# AquaLed-logic.net
KiCad netlist of a schematic drawn in EAGLE
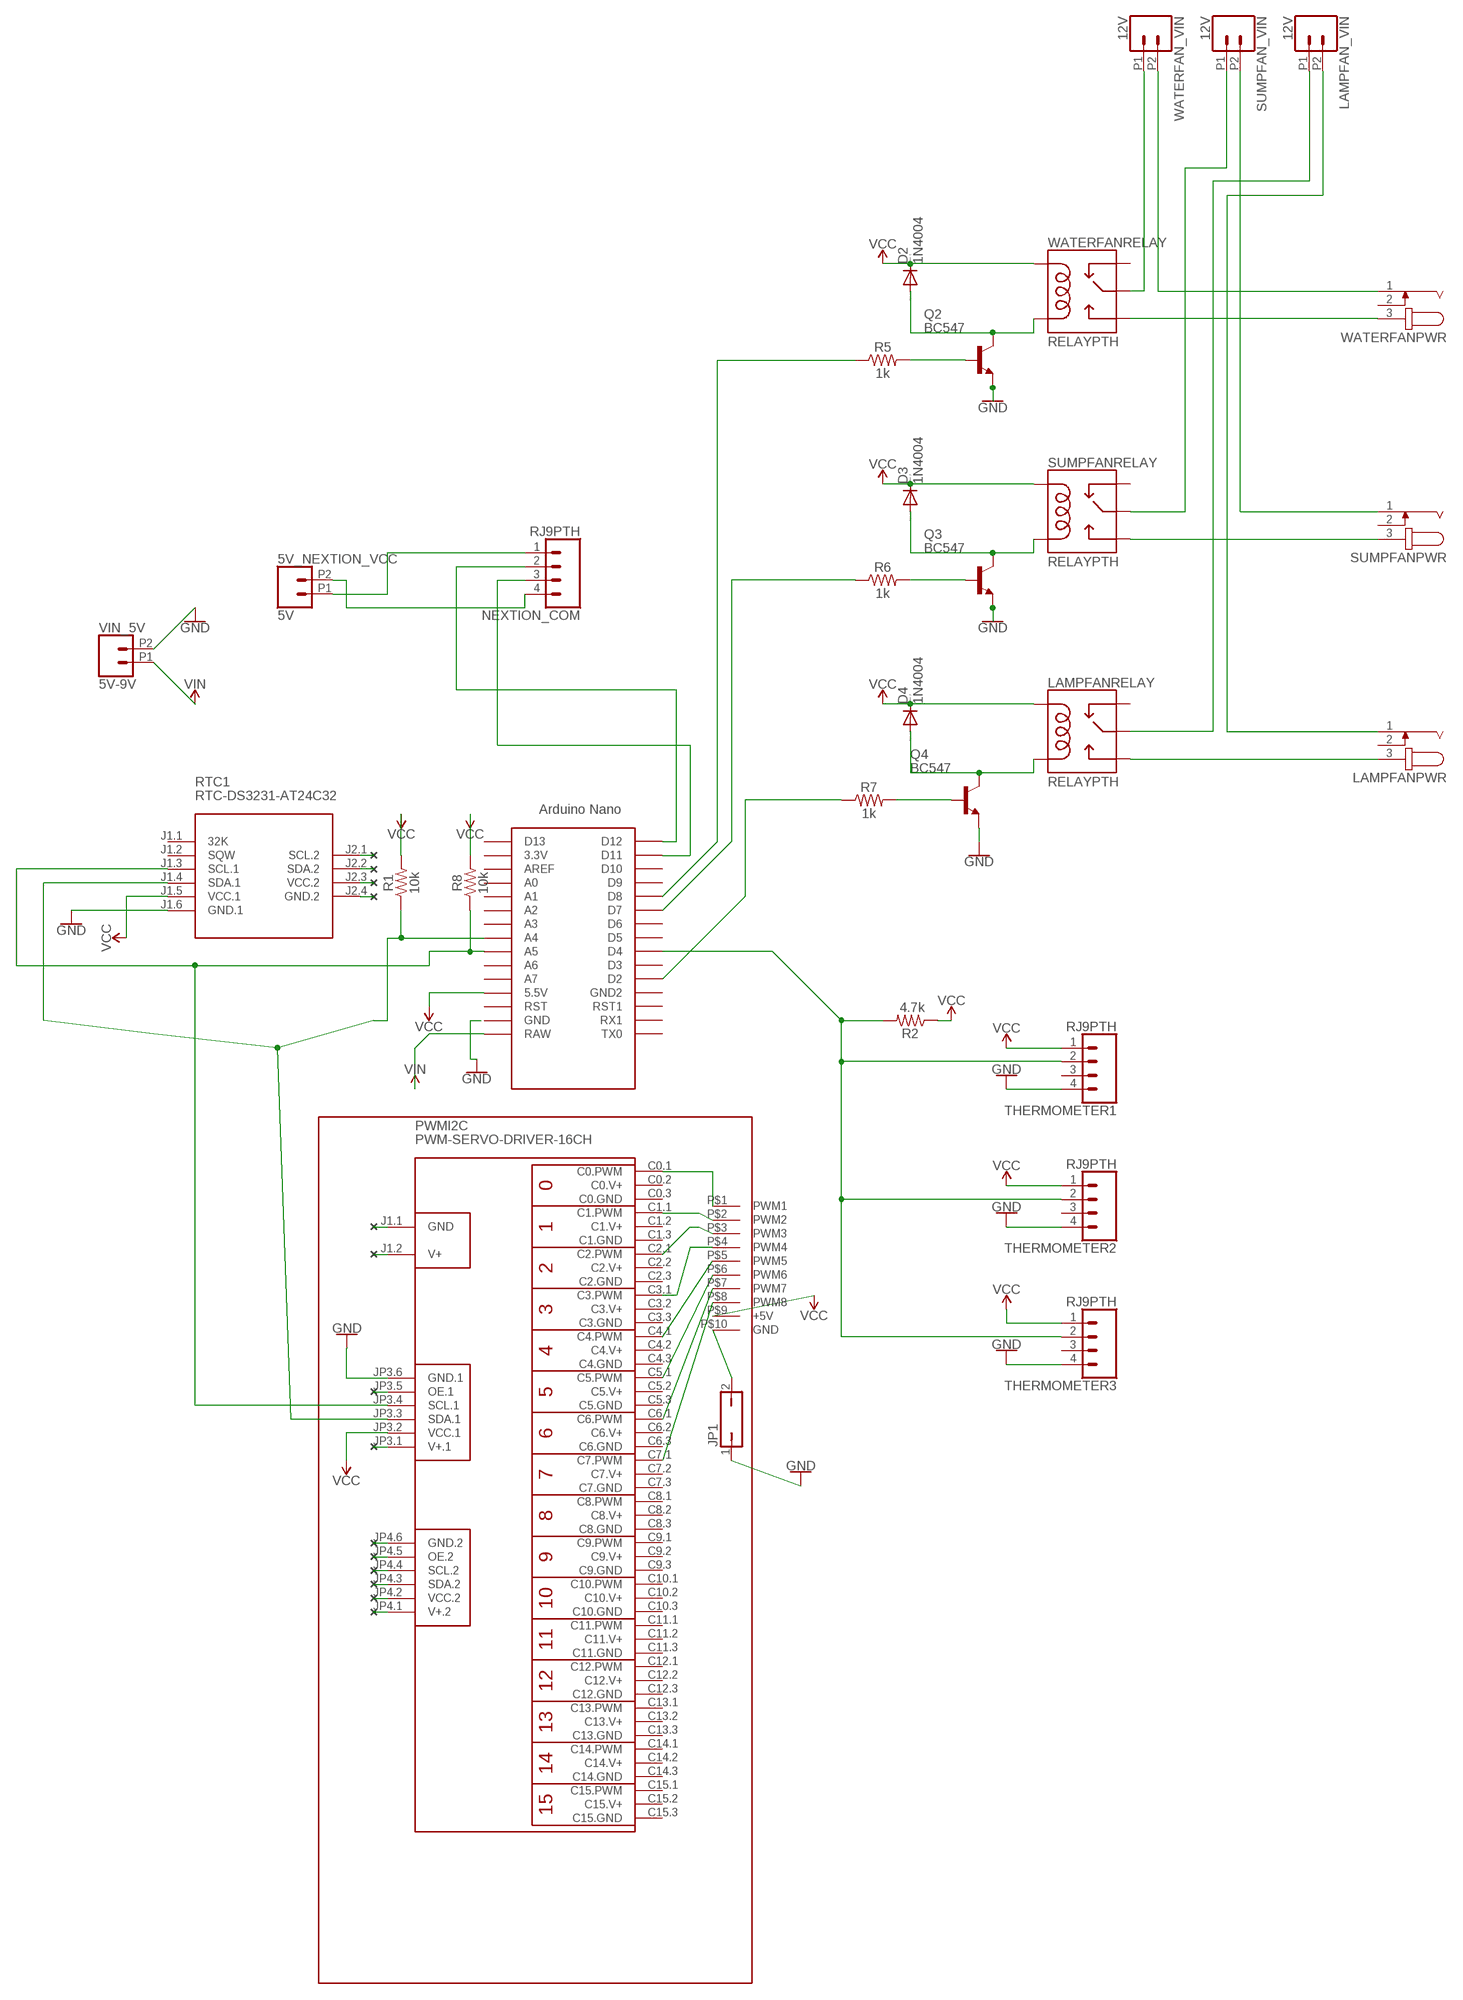
[diagram p0: schematic, sheet 1]

(export (version "E")
  (design (tool "Eeschema 10.0.6"))
  (components
    (comp (ref "5V_NEXTION_VCC")
      (value "5V")
      (footprint "eagle-import:1X02_2.54_SCREWTERM")
      (libsource (lib "eagle-import") (part "CONN_022.54MM_SCREWTERM"))
    )
    (comp (ref "D2")
      (value "1N4004")
      (footprint "eagle-import:DO41-10")
      (libsource (lib "eagle-import") (part "1N4004"))
    )
    (comp (ref "D3")
      (value "1N4004")
      (footprint "eagle-import:DO41-10")
      (libsource (lib "eagle-import") (part "1N4004"))
    )
    (comp (ref "D4")
      (value "1N4004")
      (footprint "eagle-import:DO41-10")
      (libsource (lib "eagle-import") (part "1N4004"))
    )
    (comp (ref "JP1")
      (value "JP1Q")
      (footprint "eagle-import:JP1")
      (libsource (lib "eagle-import") (part "JP1Q"))
    )
    (comp (ref "LAMPFANPWR")
      (value "JACK-PLUG1")
      (footprint "eagle-import:SPC4078")
      (libsource (lib "eagle-import") (part "JACK-PLUG1"))
    )
    (comp (ref "LAMPFANRELAY")
      (value "RELAYPTH")
      (footprint "eagle-import:SRD-05VDC-SL-C")
      (libsource (lib "eagle-import") (part "RELAYPTH"))
    )
    (comp (ref "LAMPFAN_VIN")
      (value "12V")
      (footprint "eagle-import:1X02_2.54_SCREWTERM")
      (libsource (lib "eagle-import") (part "CONN_022.54MM_SCREWTERM"))
    )
    (comp (ref "NEXTION_COM")
      (value "RJ9PTH")
      (footprint "eagle-import:RJ9")
      (libsource (lib "eagle-import") (part "RJ9PTH"))
    )
    (comp (ref "PWMI2C")
      (value "PWM-SERVO-DRIVER-16CH")
      (footprint "eagle-import:PWM-SERVO-DRIVER-16CH")
      (libsource (lib "eagle-import") (part "PWM-SERVO-DRIVER-16CH"))
    )
    (comp (ref "Q2")
      (value "BC547")
      (footprint "eagle-import:TO92")
      (libsource (lib "eagle-import") (part "BC547"))
    )
    (comp (ref "Q3")
      (value "BC547")
      (footprint "eagle-import:TO92")
      (libsource (lib "eagle-import") (part "BC547"))
    )
    (comp (ref "Q4")
      (value "BC547")
      (footprint "eagle-import:TO92")
      (libsource (lib "eagle-import") (part "BC547"))
    )
    (comp (ref "R1")
      (value "10k")
      (footprint "eagle-import:AXIAL-0.3")
      (libsource (lib "eagle-import") (part "SparkFun-Resistors_532_10KOHM-HORIZ-1/6W-5%"))
    )
    (comp (ref "R2")
      (value "4.7k")
      (footprint "eagle-import:AXIAL-0.3")
      (libsource (lib "eagle-import") (part "RESISTORAXIAL-0.3"))
    )
    (comp (ref "R5")
      (value "1k")
      (footprint "eagle-import:AXIAL-0.3")
      (libsource (lib "eagle-import") (part "10KOHM-HORIZ-1/4W-1%"))
    )
    (comp (ref "R6")
      (value "1k")
      (footprint "eagle-import:AXIAL-0.3")
      (libsource (lib "eagle-import") (part "10KOHM-HORIZ-1/4W-1%"))
    )
    (comp (ref "R7")
      (value "1k")
      (footprint "eagle-import:AXIAL-0.3")
      (libsource (lib "eagle-import") (part "10KOHM-HORIZ-1/4W-1%"))
    )
    (comp (ref "R8")
      (value "10k")
      (footprint "eagle-import:AXIAL-0.3")
      (libsource (lib "eagle-import") (part "SparkFun-Resistors_532_10KOHM-HORIZ-1/6W-5%"))
    )
    (comp (ref "RTC1")
      (value "RTC-DS3231-AT24C32")
      (footprint "eagle-import:RTC-DS3231-AT24C32")
      (fields (field (name "SPICEPREFIX") "X"))
      (libsource (lib "eagle-import") (part "RTC-DS3231-AT24C32"))
    )
    (comp (ref "SUMPFANPWR")
      (value "JACK-PLUG1")
      (footprint "eagle-import:SPC4078")
      (libsource (lib "eagle-import") (part "JACK-PLUG1"))
    )
    (comp (ref "SUMPFANRELAY")
      (value "RELAYPTH")
      (footprint "eagle-import:SRD-05VDC-SL-C")
      (libsource (lib "eagle-import") (part "RELAYPTH"))
    )
    (comp (ref "SUMPFAN_VIN")
      (value "12V")
      (footprint "eagle-import:1X02_2.54_SCREWTERM")
      (libsource (lib "eagle-import") (part "CONN_022.54MM_SCREWTERM"))
    )
    (comp (ref "THERMOMETER1")
      (value "RJ9PTH")
      (footprint "eagle-import:RJ9")
      (libsource (lib "eagle-import") (part "RJ9PTH"))
    )
    (comp (ref "THERMOMETER2")
      (value "RJ9PTH")
      (footprint "eagle-import:RJ9")
      (libsource (lib "eagle-import") (part "RJ9PTH"))
    )
    (comp (ref "THERMOMETER3")
      (value "RJ9PTH")
      (footprint "eagle-import:RJ9")
      (libsource (lib "eagle-import") (part "RJ9PTH"))
    )
    (comp (ref "U$1")
      (value "NANO")
      (footprint "eagle-import:NANO")
      (libsource (lib "eagle-import") (part "NANO"))
    )
    (comp (ref "U$29")
      (value "PCB")
      (footprint "eagle-import:PCB")
      (libsource (lib "eagle-import") (part "PCB"))
    )
    (comp (ref "VIN_5V")
      (value "5V-9V")
      (footprint "eagle-import:1X02_2.54_SCREWTERM")
      (libsource (lib "eagle-import") (part "CONN_022.54MM_SCREWTERM"))
    )
    (comp (ref "WATERFANPWR")
      (value "JACK-PLUG1")
      (footprint "eagle-import:SPC4078")
      (libsource (lib "eagle-import") (part "JACK-PLUG1"))
    )
    (comp (ref "WATERFANRELAY")
      (value "RELAYPTH")
      (footprint "eagle-import:SRD-05VDC-SL-C")
      (libsource (lib "eagle-import") (part "RELAYPTH"))
    )
    (comp (ref "WATERFAN_VIN")
      (value "12V")
      (footprint "eagle-import:1X02_2.54_SCREWTERM")
      (libsource (lib "eagle-import") (part "CONN_022.54MM_SCREWTERM"))
    )
  )
  (nets
    (net (code "1") (name "GND") (class "Default")
      (node (ref "JP1") (pin "1") (pinfunction "1_1") (pintype "passive"))
      (node (ref "PWMI2C") (pin "JP3.6") (pinfunction "GND.1_JP3.6") (pintype "power_in"))
      (node (ref "Q2") (pin "1") (pinfunction "E_1") (pintype "passive"))
      (node (ref "Q3") (pin "1") (pinfunction "E_1") (pintype "passive"))
      (node (ref "Q4") (pin "1") (pinfunction "E_1") (pintype "passive"))
      (node (ref "RTC1") (pin "J1.6") (pinfunction "GND.1_J1.6") (pintype "power_in"))
      (node (ref "THERMOMETER1") (pin "4") (pinfunction "4_4") (pintype "passive"))
      (node (ref "THERMOMETER2") (pin "4") (pinfunction "4_4") (pintype "passive"))
      (node (ref "THERMOMETER3") (pin "4") (pinfunction "4_4") (pintype "passive"))
      (node (ref "U$1") (pin "GND") (pinfunction "GND_GND") (pintype "bidirectional"))
      (node (ref "VIN_5V") (pin "P2") (pinfunction "2_P2") (pintype "passive"))
    )
    (net (code "2") (name "Net-(5V_NEXTION_VCC-1)") (class "Default")
      (node (ref "5V_NEXTION_VCC") (pin "P1") (pinfunction "1_P1") (pintype "passive"))
      (node (ref "NEXTION_COM") (pin "1") (pinfunction "1_1") (pintype "passive"))
    )
    (net (code "3") (name "Net-(5V_NEXTION_VCC-2)") (class "Default")
      (node (ref "5V_NEXTION_VCC") (pin "P2") (pinfunction "2_P2") (pintype "passive"))
      (node (ref "NEXTION_COM") (pin "4") (pinfunction "4_4") (pintype "passive"))
    )
    (net (code "4") (name "Net-(LAMPFANPWR-Pad3)") (class "Default")
      (node (ref "LAMPFANPWR") (pin "3") (pinfunction "3_3") (pintype "passive"))
      (node (ref "LAMPFANRELAY") (pin "SWOPEN") (pinfunction "SWOPEN_SWOPEN") (pintype "bidirectional"))
    )
    (net (code "5") (name "Net-(LAMPFAN_VIN-1)") (class "Default")
      (node (ref "LAMPFANRELAY") (pin "SWCOMMON") (pinfunction "SWCOMMON_SWCOMMON") (pintype "bidirectional"))
      (node (ref "LAMPFAN_VIN") (pin "P1") (pinfunction "1_P1") (pintype "passive"))
    )
    (net (code "6") (name "Net-(LAMPFAN_VIN-2)") (class "Default")
      (node (ref "LAMPFANPWR") (pin "1") (pinfunction "1_1") (pintype "passive"))
      (node (ref "LAMPFAN_VIN") (pin "P2") (pinfunction "2_P2") (pintype "passive"))
    )
    (net (code "7") (name "Net-(NEXTION_COM-Pad2)") (class "Default")
      (node (ref "NEXTION_COM") (pin "2") (pinfunction "2_2") (pintype "passive"))
      (node (ref "U$1") (pin "D12") (pinfunction "D12_D12") (pintype "bidirectional"))
    )
    (net (code "8") (name "Net-(NEXTION_COM-Pad3)") (class "Default")
      (node (ref "NEXTION_COM") (pin "3") (pinfunction "3_3") (pintype "passive"))
      (node (ref "U$1") (pin "D11") (pinfunction "D11_D11") (pintype "bidirectional"))
    )
    (net (code "9") (name "Net-(PWMI2C-C0.PWM)") (class "Default")
      (node (ref "PWMI2C") (pin "C0.1") (pinfunction "C0.PWM_C0.1") (pintype "bidirectional"))
      (node (ref "U$29") (pin "P$1") (pinfunction "PWM1_P$1") (pintype "bidirectional"))
    )
    (net (code "10") (name "Net-(PWMI2C-C1.PWM)") (class "Default")
      (node (ref "PWMI2C") (pin "C1.1") (pinfunction "C1.PWM_C1.1") (pintype "bidirectional"))
      (node (ref "U$29") (pin "P$2") (pinfunction "PWM2_P$2") (pintype "bidirectional"))
    )
    (net (code "11") (name "Net-(PWMI2C-C2.PWM)") (class "Default")
      (node (ref "PWMI2C") (pin "C2.1") (pinfunction "C2.PWM_C2.1") (pintype "bidirectional"))
      (node (ref "U$29") (pin "P$3") (pinfunction "PWM3_P$3") (pintype "bidirectional"))
    )
    (net (code "12") (name "Net-(PWMI2C-C3.PWM)") (class "Default")
      (node (ref "PWMI2C") (pin "C3.1") (pinfunction "C3.PWM_C3.1") (pintype "bidirectional"))
      (node (ref "U$29") (pin "P$4") (pinfunction "PWM4_P$4") (pintype "bidirectional"))
    )
    (net (code "13") (name "Net-(PWMI2C-C4.PWM)") (class "Default")
      (node (ref "PWMI2C") (pin "C4.1") (pinfunction "C4.PWM_C4.1") (pintype "bidirectional"))
      (node (ref "U$29") (pin "P$5") (pinfunction "PWM5_P$5") (pintype "bidirectional"))
    )
    (net (code "14") (name "Net-(PWMI2C-C5.PWM)") (class "Default")
      (node (ref "PWMI2C") (pin "C5.1") (pinfunction "C5.PWM_C5.1") (pintype "bidirectional"))
      (node (ref "U$29") (pin "P$6") (pinfunction "PWM6_P$6") (pintype "bidirectional"))
    )
    (net (code "15") (name "Net-(PWMI2C-C6.PWM)") (class "Default")
      (node (ref "PWMI2C") (pin "C6.1") (pinfunction "C6.PWM_C6.1") (pintype "bidirectional"))
      (node (ref "U$29") (pin "P$7") (pinfunction "PWM7_P$7") (pintype "bidirectional"))
    )
    (net (code "16") (name "Net-(PWMI2C-C7.PWM)") (class "Default")
      (node (ref "PWMI2C") (pin "C7.1") (pinfunction "C7.PWM_C7.1") (pintype "bidirectional"))
      (node (ref "U$29") (pin "P$8") (pinfunction "PWM8_P$8") (pintype "bidirectional"))
    )
    (net (code "17") (name "Net-(PWMI2C-SCL.1)") (class "Default")
      (node (ref "PWMI2C") (pin "JP3.4") (pinfunction "SCL.1_JP3.4") (pintype "bidirectional"))
      (node (ref "R8") (pin "P$1") (pinfunction "1_P$1") (pintype "passive"))
      (node (ref "RTC1") (pin "J1.3") (pinfunction "SCL.1_J1.3") (pintype "bidirectional"))
      (node (ref "U$1") (pin "A5") (pinfunction "A5_A5") (pintype "bidirectional"))
    )
    (net (code "18") (name "Net-(PWMI2C-SDA.1)") (class "Default")
      (node (ref "PWMI2C") (pin "JP3.3") (pinfunction "SDA.1_JP3.3") (pintype "bidirectional"))
      (node (ref "R1") (pin "P$1") (pinfunction "1_P$1") (pintype "passive"))
      (node (ref "RTC1") (pin "J1.4") (pinfunction "SDA.1_J1.4") (pintype "bidirectional"))
      (node (ref "U$1") (pin "A4") (pinfunction "A4_A4") (pintype "bidirectional"))
    )
    (net (code "19") (name "Net-(Q2-B)") (class "Default")
      (node (ref "Q2") (pin "2") (pinfunction "B_2") (pintype "passive"))
      (node (ref "R5") (pin "P$2") (pinfunction "2_P$2") (pintype "passive"))
    )
    (net (code "20") (name "Net-(Q2-C)") (class "Default")
      (node (ref "D2") (pin "A") (pinfunction "A_A") (pintype "passive"))
      (node (ref "Q2") (pin "3") (pinfunction "C_3") (pintype "passive"))
      (node (ref "WATERFANRELAY") (pin "COIL0") (pinfunction "COIL0_COIL0") (pintype "bidirectional"))
    )
    (net (code "21") (name "Net-(Q3-B)") (class "Default")
      (node (ref "Q3") (pin "2") (pinfunction "B_2") (pintype "passive"))
      (node (ref "R6") (pin "P$2") (pinfunction "2_P$2") (pintype "passive"))
    )
    (net (code "22") (name "Net-(Q3-C)") (class "Default")
      (node (ref "D3") (pin "A") (pinfunction "A_A") (pintype "passive"))
      (node (ref "Q3") (pin "3") (pinfunction "C_3") (pintype "passive"))
      (node (ref "SUMPFANRELAY") (pin "COIL0") (pinfunction "COIL0_COIL0") (pintype "bidirectional"))
    )
    (net (code "23") (name "Net-(Q4-B)") (class "Default")
      (node (ref "Q4") (pin "2") (pinfunction "B_2") (pintype "passive"))
      (node (ref "R7") (pin "P$2") (pinfunction "2_P$2") (pintype "passive"))
    )
    (net (code "24") (name "Net-(Q4-C)") (class "Default")
      (node (ref "D4") (pin "A") (pinfunction "A_A") (pintype "passive"))
      (node (ref "LAMPFANRELAY") (pin "COIL0") (pinfunction "COIL0_COIL0") (pintype "bidirectional"))
      (node (ref "Q4") (pin "3") (pinfunction "C_3") (pintype "passive"))
    )
    (net (code "25") (name "Net-(R2-2)") (class "Default")
      (node (ref "R2") (pin "P$2") (pinfunction "2_P$2") (pintype "passive"))
      (node (ref "THERMOMETER1") (pin "2") (pinfunction "2_2") (pintype "passive"))
      (node (ref "THERMOMETER2") (pin "2") (pinfunction "2_2") (pintype "passive"))
      (node (ref "THERMOMETER3") (pin "2") (pinfunction "2_2") (pintype "passive"))
      (node (ref "U$1") (pin "D4") (pinfunction "D4_D4") (pintype "bidirectional"))
    )
    (net (code "26") (name "Net-(R5-1)") (class "Default")
      (node (ref "R5") (pin "P$1") (pinfunction "1_P$1") (pintype "passive"))
      (node (ref "U$1") (pin "D8") (pinfunction "D8_D8") (pintype "bidirectional"))
    )
    (net (code "27") (name "Net-(R6-1)") (class "Default")
      (node (ref "R6") (pin "P$1") (pinfunction "1_P$1") (pintype "passive"))
      (node (ref "U$1") (pin "D7") (pinfunction "D7_D7") (pintype "bidirectional"))
    )
    (net (code "28") (name "Net-(R7-1)") (class "Default")
      (node (ref "R7") (pin "P$1") (pinfunction "1_P$1") (pintype "passive"))
      (node (ref "U$1") (pin "D2") (pinfunction "D2_D2") (pintype "bidirectional"))
    )
    (net (code "29") (name "Net-(SUMPFANPWR-Pad3)") (class "Default")
      (node (ref "SUMPFANPWR") (pin "3") (pinfunction "3_3") (pintype "passive"))
      (node (ref "SUMPFANRELAY") (pin "SWOPEN") (pinfunction "SWOPEN_SWOPEN") (pintype "bidirectional"))
    )
    (net (code "30") (name "Net-(SUMPFAN_VIN-1)") (class "Default")
      (node (ref "SUMPFANRELAY") (pin "SWCOMMON") (pinfunction "SWCOMMON_SWCOMMON") (pintype "bidirectional"))
      (node (ref "SUMPFAN_VIN") (pin "P1") (pinfunction "1_P1") (pintype "passive"))
    )
    (net (code "31") (name "Net-(SUMPFAN_VIN-2)") (class "Default")
      (node (ref "SUMPFANPWR") (pin "1") (pinfunction "1_1") (pintype "passive"))
      (node (ref "SUMPFAN_VIN") (pin "P2") (pinfunction "2_P2") (pintype "passive"))
    )
    (net (code "32") (name "Net-(U$29-GND)") (class "Default")
      (node (ref "JP1") (pin "2") (pinfunction "2_2") (pintype "passive"))
      (node (ref "U$29") (pin "P$10") (pinfunction "GND_P$10") (pintype "power_in"))
    )
    (net (code "33") (name "Net-(WATERFANPWR-Pad3)") (class "Default")
      (node (ref "WATERFANPWR") (pin "3") (pinfunction "3_3") (pintype "passive"))
      (node (ref "WATERFANRELAY") (pin "SWOPEN") (pinfunction "SWOPEN_SWOPEN") (pintype "bidirectional"))
    )
    (net (code "34") (name "Net-(WATERFAN_VIN-1)") (class "Default")
      (node (ref "WATERFANRELAY") (pin "SWCOMMON") (pinfunction "SWCOMMON_SWCOMMON") (pintype "bidirectional"))
      (node (ref "WATERFAN_VIN") (pin "P1") (pinfunction "1_P1") (pintype "passive"))
    )
    (net (code "35") (name "Net-(WATERFAN_VIN-2)") (class "Default")
      (node (ref "WATERFANPWR") (pin "1") (pinfunction "1_1") (pintype "passive"))
      (node (ref "WATERFAN_VIN") (pin "P2") (pinfunction "2_P2") (pintype "passive"))
    )
    (net (code "36") (name "VCC") (class "Default")
      (node (ref "D2") (pin "C") (pinfunction "C_C") (pintype "passive"))
      (node (ref "D3") (pin "C") (pinfunction "C_C") (pintype "passive"))
      (node (ref "D4") (pin "C") (pinfunction "C_C") (pintype "passive"))
      (node (ref "LAMPFANRELAY") (pin "COIL1") (pinfunction "COIL1_COIL1") (pintype "bidirectional"))
      (node (ref "PWMI2C") (pin "JP3.2") (pinfunction "VCC.1_JP3.2") (pintype "power_in"))
      (node (ref "R1") (pin "P$2") (pinfunction "2_P$2") (pintype "passive"))
      (node (ref "R2") (pin "P$1") (pinfunction "1_P$1") (pintype "passive"))
      (node (ref "R8") (pin "P$2") (pinfunction "2_P$2") (pintype "passive"))
      (node (ref "RTC1") (pin "J1.5") (pinfunction "VCC.1_J1.5") (pintype "power_in"))
      (node (ref "SUMPFANRELAY") (pin "COIL1") (pinfunction "COIL1_COIL1") (pintype "bidirectional"))
      (node (ref "THERMOMETER1") (pin "1") (pinfunction "1_1") (pintype "passive"))
      (node (ref "THERMOMETER2") (pin "1") (pinfunction "1_1") (pintype "passive"))
      (node (ref "THERMOMETER3") (pin "1") (pinfunction "1_1") (pintype "passive"))
      (node (ref "U$1") (pin "5V") (pinfunction "5.5V_5V") (pintype "bidirectional"))
      (node (ref "U$29") (pin "P$9") (pinfunction "+5V_P$9") (pintype "power_in"))
      (node (ref "WATERFANRELAY") (pin "COIL1") (pinfunction "COIL1_COIL1") (pintype "bidirectional"))
    )
    (net (code "37") (name "VIN") (class "Default")
      (node (ref "U$1") (pin "RAW") (pinfunction "RAW_RAW") (pintype "bidirectional"))
      (node (ref "VIN_5V") (pin "P1") (pinfunction "1_P1") (pintype "passive"))
    )
    (net (code "38") (name "unconnected-(LAMPFANPWR-Pad2)") (class "Default")
      (node (ref "LAMPFANPWR") (pin "2") (pinfunction "2_2") (pintype "passive"))
    )
    (net (code "39") (name "unconnected-(LAMPFANRELAY-SWCLOSE-PadSWCLOSED)") (class "Default")
      (node (ref "LAMPFANRELAY") (pin "SWCLOSED") (pinfunction "SWCLOSE_SWCLOSED") (pintype "bidirectional"))
    )
    (net (code "40") (name "unconnected-(PWMI2C-C0.GND-PadC0.3)") (class "Default")
      (node (ref "PWMI2C") (pin "C0.3") (pinfunction "C0.GND_C0.3") (pintype "bidirectional"))
    )
    (net (code "41") (name "unconnected-(PWMI2C-C0.V+-PadC0.2)") (class "Default")
      (node (ref "PWMI2C") (pin "C0.2") (pinfunction "C0.V+_C0.2") (pintype "bidirectional"))
    )
    (net (code "42") (name "unconnected-(PWMI2C-C1.GND-PadC1.3)") (class "Default")
      (node (ref "PWMI2C") (pin "C1.3") (pinfunction "C1.GND_C1.3") (pintype "bidirectional"))
    )
    (net (code "43") (name "unconnected-(PWMI2C-C1.V+-PadC1.2)") (class "Default")
      (node (ref "PWMI2C") (pin "C1.2") (pinfunction "C1.V+_C1.2") (pintype "bidirectional"))
    )
    (net (code "44") (name "unconnected-(PWMI2C-C2.GND-PadC2.3)") (class "Default")
      (node (ref "PWMI2C") (pin "C2.3") (pinfunction "C2.GND_C2.3") (pintype "bidirectional"))
    )
    (net (code "45") (name "unconnected-(PWMI2C-C2.V+-PadC2.2)") (class "Default")
      (node (ref "PWMI2C") (pin "C2.2") (pinfunction "C2.V+_C2.2") (pintype "bidirectional"))
    )
    (net (code "46") (name "unconnected-(PWMI2C-C3.GND-PadC3.3)") (class "Default")
      (node (ref "PWMI2C") (pin "C3.3") (pinfunction "C3.GND_C3.3") (pintype "bidirectional"))
    )
    (net (code "47") (name "unconnected-(PWMI2C-C3.V+-PadC3.2)") (class "Default")
      (node (ref "PWMI2C") (pin "C3.2") (pinfunction "C3.V+_C3.2") (pintype "bidirectional"))
    )
    (net (code "48") (name "unconnected-(PWMI2C-C4.GND-PadC4.3)") (class "Default")
      (node (ref "PWMI2C") (pin "C4.3") (pinfunction "C4.GND_C4.3") (pintype "bidirectional"))
    )
    (net (code "49") (name "unconnected-(PWMI2C-C4.V+-PadC4.2)") (class "Default")
      (node (ref "PWMI2C") (pin "C4.2") (pinfunction "C4.V+_C4.2") (pintype "bidirectional"))
    )
    (net (code "50") (name "unconnected-(PWMI2C-C5.GND-PadC5.3)") (class "Default")
      (node (ref "PWMI2C") (pin "C5.3") (pinfunction "C5.GND_C5.3") (pintype "bidirectional"))
    )
    (net (code "51") (name "unconnected-(PWMI2C-C5.V+-PadC5.2)") (class "Default")
      (node (ref "PWMI2C") (pin "C5.2") (pinfunction "C5.V+_C5.2") (pintype "bidirectional"))
    )
    (net (code "52") (name "unconnected-(PWMI2C-C6.GND-PadC6.3)") (class "Default")
      (node (ref "PWMI2C") (pin "C6.3") (pinfunction "C6.GND_C6.3") (pintype "bidirectional"))
    )
    (net (code "53") (name "unconnected-(PWMI2C-C6.V+-PadC6.2)") (class "Default")
      (node (ref "PWMI2C") (pin "C6.2") (pinfunction "C6.V+_C6.2") (pintype "bidirectional"))
    )
    (net (code "54") (name "unconnected-(PWMI2C-C7.GND-PadC7.3)") (class "Default")
      (node (ref "PWMI2C") (pin "C7.3") (pinfunction "C7.GND_C7.3") (pintype "bidirectional"))
    )
    (net (code "55") (name "unconnected-(PWMI2C-C7.V+-PadC7.2)") (class "Default")
      (node (ref "PWMI2C") (pin "C7.2") (pinfunction "C7.V+_C7.2") (pintype "bidirectional"))
    )
    (net (code "56") (name "unconnected-(PWMI2C-C8.GND-PadC8.3)") (class "Default")
      (node (ref "PWMI2C") (pin "C8.3") (pinfunction "C8.GND_C8.3") (pintype "bidirectional"))
    )
    (net (code "57") (name "unconnected-(PWMI2C-C8.PWM-PadC8.1)") (class "Default")
      (node (ref "PWMI2C") (pin "C8.1") (pinfunction "C8.PWM_C8.1") (pintype "bidirectional"))
    )
    (net (code "58") (name "unconnected-(PWMI2C-C8.V+-PadC8.2)") (class "Default")
      (node (ref "PWMI2C") (pin "C8.2") (pinfunction "C8.V+_C8.2") (pintype "bidirectional"))
    )
    (net (code "59") (name "unconnected-(PWMI2C-C9.GND-PadC9.3)") (class "Default")
      (node (ref "PWMI2C") (pin "C9.3") (pinfunction "C9.GND_C9.3") (pintype "bidirectional"))
    )
    (net (code "60") (name "unconnected-(PWMI2C-C9.PWM-PadC9.1)") (class "Default")
      (node (ref "PWMI2C") (pin "C9.1") (pinfunction "C9.PWM_C9.1") (pintype "bidirectional"))
    )
    (net (code "61") (name "unconnected-(PWMI2C-C9.V+-PadC9.2)") (class "Default")
      (node (ref "PWMI2C") (pin "C9.2") (pinfunction "C9.V+_C9.2") (pintype "bidirectional"))
    )
    (net (code "62") (name "unconnected-(PWMI2C-C10.GND-PadC10.3)") (class "Default")
      (node (ref "PWMI2C") (pin "C10.3") (pinfunction "C10.GND_C10.3") (pintype "bidirectional"))
    )
    (net (code "63") (name "unconnected-(PWMI2C-C10.PWM-PadC10.1)") (class "Default")
      (node (ref "PWMI2C") (pin "C10.1") (pinfunction "C10.PWM_C10.1") (pintype "bidirectional"))
    )
    (net (code "64") (name "unconnected-(PWMI2C-C10.V+-PadC10.2)") (class "Default")
      (node (ref "PWMI2C") (pin "C10.2") (pinfunction "C10.V+_C10.2") (pintype "bidirectional"))
    )
    (net (code "65") (name "unconnected-(PWMI2C-C11.GND-PadC11.3)") (class "Default")
      (node (ref "PWMI2C") (pin "C11.3") (pinfunction "C11.GND_C11.3") (pintype "bidirectional"))
    )
    (net (code "66") (name "unconnected-(PWMI2C-C11.PWM-PadC11.1)") (class "Default")
      (node (ref "PWMI2C") (pin "C11.1") (pinfunction "C11.PWM_C11.1") (pintype "bidirectional"))
    )
    (net (code "67") (name "unconnected-(PWMI2C-C11.V+-PadC11.2)") (class "Default")
      (node (ref "PWMI2C") (pin "C11.2") (pinfunction "C11.V+_C11.2") (pintype "bidirectional"))
    )
    (net (code "68") (name "unconnected-(PWMI2C-C12.GND-PadC12.3)") (class "Default")
      (node (ref "PWMI2C") (pin "C12.3") (pinfunction "C12.GND_C12.3") (pintype "bidirectional"))
    )
    (net (code "69") (name "unconnected-(PWMI2C-C12.PWM-PadC12.1)") (class "Default")
      (node (ref "PWMI2C") (pin "C12.1") (pinfunction "C12.PWM_C12.1") (pintype "bidirectional"))
    )
    (net (code "70") (name "unconnected-(PWMI2C-C12.V+-PadC12.2)") (class "Default")
      (node (ref "PWMI2C") (pin "C12.2") (pinfunction "C12.V+_C12.2") (pintype "bidirectional"))
    )
    (net (code "71") (name "unconnected-(PWMI2C-C13.GND-PadC13.3)") (class "Default")
      (node (ref "PWMI2C") (pin "C13.3") (pinfunction "C13.GND_C13.3") (pintype "bidirectional"))
    )
    (net (code "72") (name "unconnected-(PWMI2C-C13.PWM-PadC13.1)") (class "Default")
      (node (ref "PWMI2C") (pin "C13.1") (pinfunction "C13.PWM_C13.1") (pintype "bidirectional"))
    )
    (net (code "73") (name "unconnected-(PWMI2C-C13.V+-PadC13.2)") (class "Default")
      (node (ref "PWMI2C") (pin "C13.2") (pinfunction "C13.V+_C13.2") (pintype "bidirectional"))
    )
    (net (code "74") (name "unconnected-(PWMI2C-C14.GND-PadC14.3)") (class "Default")
      (node (ref "PWMI2C") (pin "C14.3") (pinfunction "C14.GND_C14.3") (pintype "bidirectional"))
    )
    (net (code "75") (name "unconnected-(PWMI2C-C14.PWM-PadC14.1)") (class "Default")
      (node (ref "PWMI2C") (pin "C14.1") (pinfunction "C14.PWM_C14.1") (pintype "bidirectional"))
    )
    (net (code "76") (name "unconnected-(PWMI2C-C14.V+-PadC14.2)") (class "Default")
      (node (ref "PWMI2C") (pin "C14.2") (pinfunction "C14.V+_C14.2") (pintype "bidirectional"))
    )
    (net (code "77") (name "unconnected-(PWMI2C-C15.GND-PadC15.3)") (class "Default")
      (node (ref "PWMI2C") (pin "C15.3") (pinfunction "C15.GND_C15.3") (pintype "bidirectional"))
    )
    (net (code "78") (name "unconnected-(PWMI2C-C15.PWM-PadC15.1)") (class "Default")
      (node (ref "PWMI2C") (pin "C15.1") (pinfunction "C15.PWM_C15.1") (pintype "bidirectional"))
    )
    (net (code "79") (name "unconnected-(PWMI2C-C15.V+-PadC15.2)") (class "Default")
      (node (ref "PWMI2C") (pin "C15.2") (pinfunction "C15.V+_C15.2") (pintype "bidirectional"))
    )
    (net (code "80") (name "unconnected-(PWMI2C-GND-PadJ1.1)") (class "Default")
      (node (ref "PWMI2C") (pin "J1.1") (pinfunction "GND_J1.1") (pintype "power_in"))
    )
    (net (code "81") (name "unconnected-(PWMI2C-GND.2-PadJP4.6)") (class "Default")
      (node (ref "PWMI2C") (pin "JP4.6") (pinfunction "GND.2_JP4.6") (pintype "power_in"))
    )
    (net (code "82") (name "unconnected-(PWMI2C-OE.1-PadJP3.5)") (class "Default")
      (node (ref "PWMI2C") (pin "JP3.5") (pinfunction "OE.1_JP3.5") (pintype "bidirectional"))
    )
    (net (code "83") (name "unconnected-(PWMI2C-OE.2-PadJP4.5)") (class "Default")
      (node (ref "PWMI2C") (pin "JP4.5") (pinfunction "OE.2_JP4.5") (pintype "bidirectional"))
    )
    (net (code "84") (name "unconnected-(PWMI2C-SCL.2-PadJP4.4)") (class "Default")
      (node (ref "PWMI2C") (pin "JP4.4") (pinfunction "SCL.2_JP4.4") (pintype "bidirectional"))
    )
    (net (code "85") (name "unconnected-(PWMI2C-SDA.2-PadJP4.3)") (class "Default")
      (node (ref "PWMI2C") (pin "JP4.3") (pinfunction "SDA.2_JP4.3") (pintype "bidirectional"))
    )
    (net (code "86") (name "unconnected-(PWMI2C-V+-PadJ1.2)") (class "Default")
      (node (ref "PWMI2C") (pin "J1.2") (pinfunction "V+_J1.2") (pintype "power_in"))
    )
    (net (code "87") (name "unconnected-(PWMI2C-V+.1-PadJP3.1)") (class "Default")
      (node (ref "PWMI2C") (pin "JP3.1") (pinfunction "V+.1_JP3.1") (pintype "power_in"))
    )
    (net (code "88") (name "unconnected-(PWMI2C-V+.2-PadJP4.1)") (class "Default")
      (node (ref "PWMI2C") (pin "JP4.1") (pinfunction "V+.2_JP4.1") (pintype "power_in"))
    )
    (net (code "89") (name "unconnected-(PWMI2C-VCC.2-PadJP4.2)") (class "Default")
      (node (ref "PWMI2C") (pin "JP4.2") (pinfunction "VCC.2_JP4.2") (pintype "power_in"))
    )
    (net (code "90") (name "unconnected-(RTC1-32K-PadJ1.1)") (class "Default")
      (node (ref "RTC1") (pin "J1.1") (pinfunction "32K_J1.1") (pintype "bidirectional"))
    )
    (net (code "91") (name "unconnected-(RTC1-GND.2-PadJ2.4)") (class "Default")
      (node (ref "RTC1") (pin "J2.4") (pinfunction "GND.2_J2.4") (pintype "power_in"))
    )
    (net (code "92") (name "unconnected-(RTC1-SCL.2-PadJ2.1)") (class "Default")
      (node (ref "RTC1") (pin "J2.1") (pinfunction "SCL.2_J2.1") (pintype "bidirectional"))
    )
    (net (code "93") (name "unconnected-(RTC1-SDA.2-PadJ2.2)") (class "Default")
      (node (ref "RTC1") (pin "J2.2") (pinfunction "SDA.2_J2.2") (pintype "bidirectional"))
    )
    (net (code "94") (name "unconnected-(RTC1-SQW-PadJ1.2)") (class "Default")
      (node (ref "RTC1") (pin "J1.2") (pinfunction "SQW_J1.2") (pintype "bidirectional"))
    )
    (net (code "95") (name "unconnected-(RTC1-VCC.2-PadJ2.3)") (class "Default")
      (node (ref "RTC1") (pin "J2.3") (pinfunction "VCC.2_J2.3") (pintype "power_in"))
    )
    (net (code "96") (name "unconnected-(SUMPFANPWR-Pad2)") (class "Default")
      (node (ref "SUMPFANPWR") (pin "2") (pinfunction "2_2") (pintype "passive"))
    )
    (net (code "97") (name "unconnected-(SUMPFANRELAY-SWCLOSE-PadSWCLOSED)") (class "Default")
      (node (ref "SUMPFANRELAY") (pin "SWCLOSED") (pinfunction "SWCLOSE_SWCLOSED") (pintype "bidirectional"))
    )
    (net (code "98") (name "unconnected-(THERMOMETER1-Pad3)") (class "Default")
      (node (ref "THERMOMETER1") (pin "3") (pinfunction "3_3") (pintype "passive"))
    )
    (net (code "99") (name "unconnected-(THERMOMETER2-Pad3)") (class "Default")
      (node (ref "THERMOMETER2") (pin "3") (pinfunction "3_3") (pintype "passive"))
    )
    (net (code "100") (name "unconnected-(THERMOMETER3-Pad3)") (class "Default")
      (node (ref "THERMOMETER3") (pin "3") (pinfunction "3_3") (pintype "passive"))
    )
    (net (code "101") (name "unconnected-(U$1-GND2-PadGND1)") (class "Default")
      (node (ref "U$1") (pin "GND1") (pinfunction "GND2_GND1") (pintype "bidirectional"))
    )
    (net (code "102") (name "unconnected-(U$1-Pad3.3V)") (class "Default")
      (node (ref "U$1") (pin "3.3V") (pinfunction "3.3V_3.3V") (pintype "bidirectional"))
    )
    (net (code "103") (name "unconnected-(U$1-PadA0)") (class "Default")
      (node (ref "U$1") (pin "A0") (pinfunction "A0_A0") (pintype "bidirectional"))
    )
    (net (code "104") (name "unconnected-(U$1-PadA1)") (class "Default")
      (node (ref "U$1") (pin "A1") (pinfunction "A1_A1") (pintype "bidirectional"))
    )
    (net (code "105") (name "unconnected-(U$1-PadA2)") (class "Default")
      (node (ref "U$1") (pin "A2") (pinfunction "A2_A2") (pintype "bidirectional"))
    )
    (net (code "106") (name "unconnected-(U$1-PadA3)") (class "Default")
      (node (ref "U$1") (pin "A3") (pinfunction "A3_A3") (pintype "bidirectional"))
    )
    (net (code "107") (name "unconnected-(U$1-PadA6)") (class "Default")
      (node (ref "U$1") (pin "A6") (pinfunction "A6_A6") (pintype "bidirectional"))
    )
    (net (code "108") (name "unconnected-(U$1-PadA7)") (class "Default")
      (node (ref "U$1") (pin "A7") (pinfunction "A7_A7") (pintype "bidirectional"))
    )
    (net (code "109") (name "unconnected-(U$1-PadAREF)") (class "Default")
      (node (ref "U$1") (pin "AREF") (pinfunction "AREF_AREF") (pintype "bidirectional"))
    )
    (net (code "110") (name "unconnected-(U$1-PadD3)") (class "Default")
      (node (ref "U$1") (pin "D3") (pinfunction "D3_D3") (pintype "bidirectional"))
    )
    (net (code "111") (name "unconnected-(U$1-PadD5)") (class "Default")
      (node (ref "U$1") (pin "D5") (pinfunction "D5_D5") (pintype "bidirectional"))
    )
    (net (code "112") (name "unconnected-(U$1-PadD6)") (class "Default")
      (node (ref "U$1") (pin "D6") (pinfunction "D6_D6") (pintype "bidirectional"))
    )
    (net (code "113") (name "unconnected-(U$1-PadD9)") (class "Default")
      (node (ref "U$1") (pin "D9") (pinfunction "D9_D9") (pintype "bidirectional"))
    )
    (net (code "114") (name "unconnected-(U$1-PadD10)") (class "Default")
      (node (ref "U$1") (pin "D10") (pinfunction "D10_D10") (pintype "bidirectional"))
    )
    (net (code "115") (name "unconnected-(U$1-PadD13)") (class "Default")
      (node (ref "U$1") (pin "D13") (pinfunction "D13_D13") (pintype "bidirectional"))
    )
    (net (code "116") (name "unconnected-(U$1-PadICSP1)") (class "Default")
      (node (ref "U$1") (pin "ICSP1") (pinfunction "ICSP1_ICSP1") (pintype "bidirectional"))
    )
    (net (code "117") (name "unconnected-(U$1-PadICSP2)") (class "Default")
      (node (ref "U$1") (pin "ICSP2") (pinfunction "ICSP2_ICSP2") (pintype "bidirectional"))
    )
    (net (code "118") (name "unconnected-(U$1-PadICSP3)") (class "Default")
      (node (ref "U$1") (pin "ICSP3") (pinfunction "ICSP3_ICSP3") (pintype "bidirectional"))
    )
    (net (code "119") (name "unconnected-(U$1-PadICSP4)") (class "Default")
      (node (ref "U$1") (pin "ICSP4") (pinfunction "ICSP4_ICSP4") (pintype "bidirectional"))
    )
    (net (code "120") (name "unconnected-(U$1-PadICSP5)") (class "Default")
      (node (ref "U$1") (pin "ICSP5") (pinfunction "ICSP5_ICSP5") (pintype "bidirectional"))
    )
    (net (code "121") (name "unconnected-(U$1-PadICSP6)") (class "Default")
      (node (ref "U$1") (pin "ICSP6") (pinfunction "ICSP6_ICSP6") (pintype "bidirectional"))
    )
    (net (code "122") (name "unconnected-(U$1-PadRST)") (class "Default")
      (node (ref "U$1") (pin "RST") (pinfunction "RST_RST") (pintype "bidirectional"))
    )
    (net (code "123") (name "unconnected-(U$1-PadRST1)") (class "Default")
      (node (ref "U$1") (pin "RST1") (pinfunction "RST1_RST1") (pintype "bidirectional"))
    )
    (net (code "124") (name "unconnected-(U$1-PadRX1)") (class "Default")
      (node (ref "U$1") (pin "RX1") (pinfunction "RX1_RX1") (pintype "bidirectional"))
    )
    (net (code "125") (name "unconnected-(U$1-PadTX0)") (class "Default")
      (node (ref "U$1") (pin "TX0") (pinfunction "TX0_TX0") (pintype "bidirectional"))
    )
    (net (code "126") (name "unconnected-(WATERFANPWR-Pad2)") (class "Default")
      (node (ref "WATERFANPWR") (pin "2") (pinfunction "2_2") (pintype "passive"))
    )
    (net (code "127") (name "unconnected-(WATERFANRELAY-SWCLOSE-PadSWCLOSED)") (class "Default")
      (node (ref "WATERFANRELAY") (pin "SWCLOSED") (pinfunction "SWCLOSE_SWCLOSED") (pintype "bidirectional"))
    )
  )
)
